# ADC.net
KiCad netlist of a schematic drawn in Altium Designer
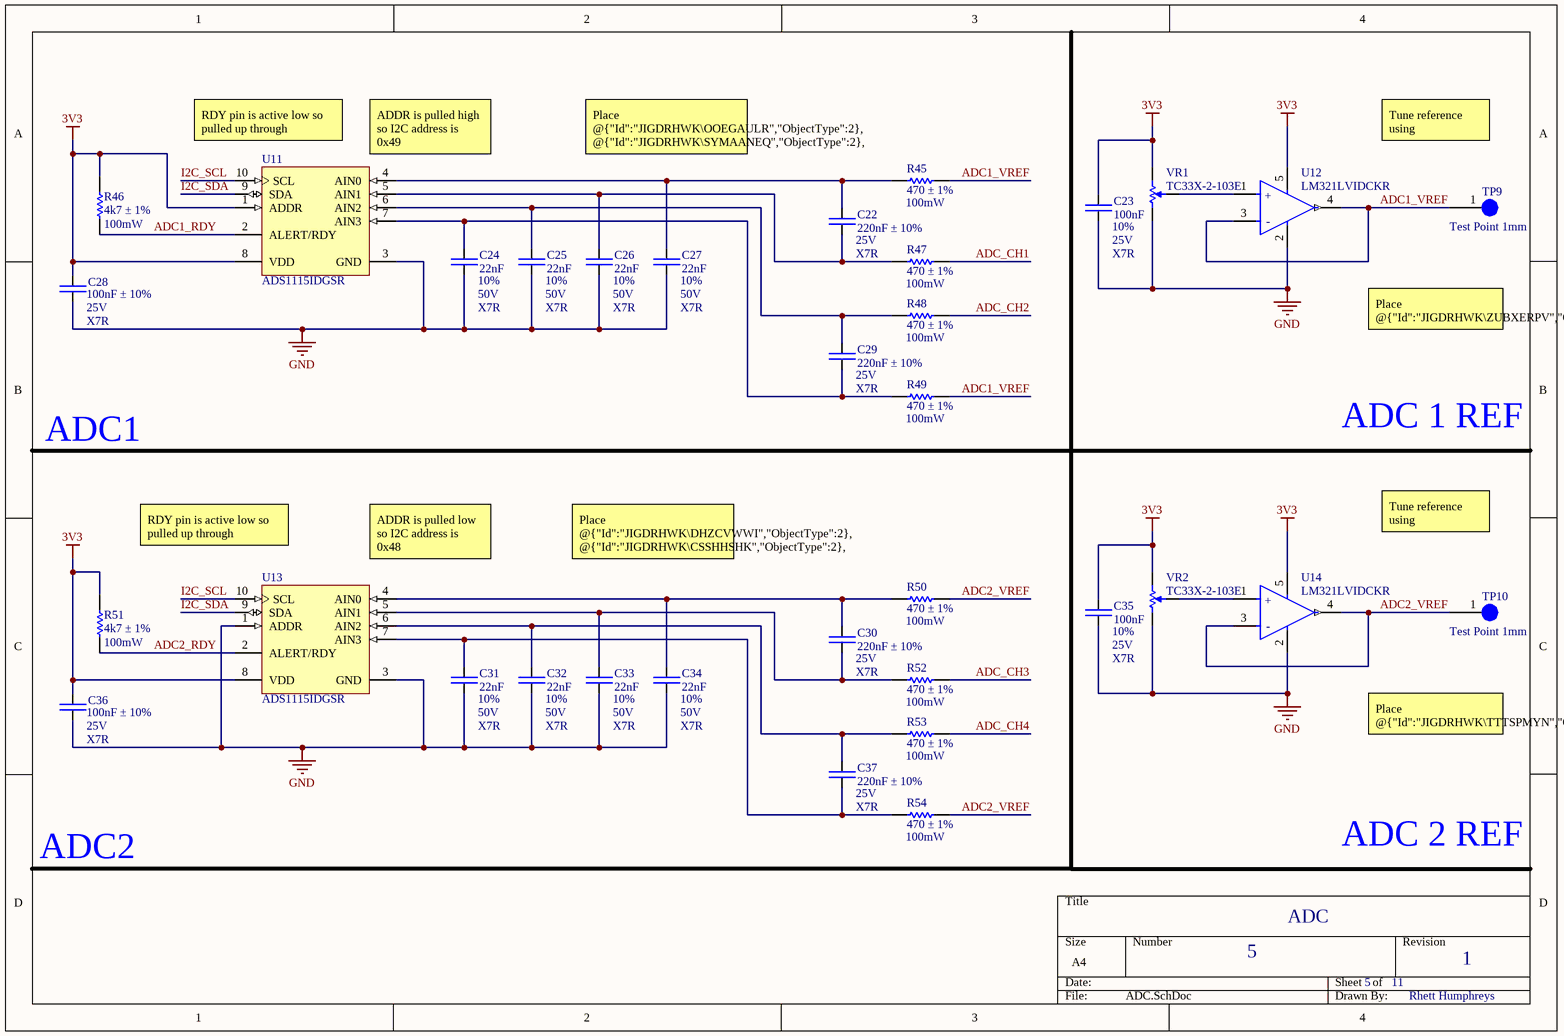
[diagram p0: ADC.SchDoc]

(export (version "E")
  (design (tool "Eeschema 10.0.6"))
  (components
    (comp (ref "C22")
      (value "220nF ± 10%")
      (footprint "CAP-0603")
      (description "Capacitor chip unpolarized. 0603")
      (libsource (lib "Master") (part "CAP-0603"))
    )
    (comp (ref "C23")
      (value "100nF")
      (footprint "CAP-0603")
      (description "Capacitor chip unpolarized. 0603")
      (libsource (lib "Master") (part "CAP-0603"))
    )
    (comp (ref "C24")
      (value "22nF")
      (footprint "CAP-0603")
      (description "Capacitor chip unpolarized. 0603")
      (libsource (lib "Master") (part "CAP-0603"))
    )
    (comp (ref "C25")
      (value "22nF")
      (footprint "CAP-0603")
      (description "Capacitor chip unpolarized. 0603")
      (libsource (lib "Master") (part "CAP-0603"))
    )
    (comp (ref "C26")
      (value "22nF")
      (footprint "CAP-0603")
      (description "Capacitor chip unpolarized. 0603")
      (libsource (lib "Master") (part "CAP-0603"))
    )
    (comp (ref "C27")
      (value "22nF")
      (footprint "CAP-0603")
      (description "Capacitor chip unpolarized. 0603")
      (libsource (lib "Master") (part "CAP-0603"))
    )
    (comp (ref "C28")
      (value "100nF ± 10%")
      (footprint "CAP-0603")
      (description "Capacitor chip unpolarized. 0603")
      (libsource (lib "Master") (part "CAP-0603"))
    )
    (comp (ref "C29")
      (value "220nF ± 10%")
      (footprint "CAP-0603")
      (description "Capacitor chip unpolarized. 0603")
      (libsource (lib "Master") (part "CAP-0603"))
    )
    (comp (ref "C30")
      (value "220nF ± 10%")
      (footprint "CAP-0603")
      (description "Capacitor chip unpolarized. 0603")
      (libsource (lib "Master") (part "CAP-0603"))
    )
    (comp (ref "C31")
      (value "22nF")
      (footprint "CAP-0603")
      (description "Capacitor chip unpolarized. 0603")
      (libsource (lib "Master") (part "CAP-0603"))
    )
    (comp (ref "C32")
      (value "22nF")
      (footprint "CAP-0603")
      (description "Capacitor chip unpolarized. 0603")
      (libsource (lib "Master") (part "CAP-0603"))
    )
    (comp (ref "C33")
      (value "22nF")
      (footprint "CAP-0603")
      (description "Capacitor chip unpolarized. 0603")
      (libsource (lib "Master") (part "CAP-0603"))
    )
    (comp (ref "C34")
      (value "22nF")
      (footprint "CAP-0603")
      (description "Capacitor chip unpolarized. 0603")
      (libsource (lib "Master") (part "CAP-0603"))
    )
    (comp (ref "C35")
      (value "100nF")
      (footprint "CAP-0603")
      (description "Capacitor chip unpolarized. 0603")
      (libsource (lib "Master") (part "CAP-0603"))
    )
    (comp (ref "C36")
      (value "100nF ± 10%")
      (footprint "CAP-0603")
      (description "Capacitor chip unpolarized. 0603")
      (libsource (lib "Master") (part "CAP-0603"))
    )
    (comp (ref "C37")
      (value "220nF ± 10%")
      (footprint "CAP-0603")
      (description "Capacitor chip unpolarized. 0603")
      (libsource (lib "Master") (part "CAP-0603"))
    )
    (comp (ref "R45")
      (value "470 ± 1%")
      (footprint "RES-0603")
      (description "Resistor chip. 0603")
      (libsource (lib "Master") (part "RES-0603"))
    )
    (comp (ref "R46")
      (value "4k7 ± 1%")
      (footprint "RES-0603")
      (description "Resistor chip. 0603")
      (libsource (lib "Master") (part "RES-0603"))
    )
    (comp (ref "R47")
      (value "470 ± 1%")
      (footprint "RES-0603")
      (description "Resistor chip. 0603")
      (libsource (lib "Master") (part "RES-0603"))
    )
    (comp (ref "R48")
      (value "470 ± 1%")
      (footprint "RES-0603")
      (description "Resistor chip. 0603")
      (libsource (lib "Master") (part "RES-0603"))
    )
    (comp (ref "R49")
      (value "470 ± 1%")
      (footprint "RES-0603")
      (description "Resistor chip. 0603")
      (libsource (lib "Master") (part "RES-0603"))
    )
    (comp (ref "R50")
      (value "470 ± 1%")
      (footprint "RES-0603")
      (description "Resistor chip. 0603")
      (libsource (lib "Master") (part "RES-0603"))
    )
    (comp (ref "R51")
      (value "4k7 ± 1%")
      (footprint "RES-0603")
      (description "Resistor chip. 0603")
      (libsource (lib "Master") (part "RES-0603"))
    )
    (comp (ref "R52")
      (value "470 ± 1%")
      (footprint "RES-0603")
      (description "Resistor chip. 0603")
      (libsource (lib "Master") (part "RES-0603"))
    )
    (comp (ref "R53")
      (value "470 ± 1%")
      (footprint "RES-0603")
      (description "Resistor chip. 0603")
      (libsource (lib "Master") (part "RES-0603"))
    )
    (comp (ref "R54")
      (value "470 ± 1%")
      (footprint "RES-0603")
      (description "Resistor chip. 0603")
      (libsource (lib "Master") (part "RES-0603"))
    )
    (comp (ref "TP9")
      (value "Test Point 1mm")
      (footprint "Test Point 1mm")
      (libsource (lib "Master") (part "Test Point 1mm"))
    )
    (comp (ref "TP10")
      (value "Test Point 1mm")
      (footprint "Test Point 1mm")
      (libsource (lib "Master") (part "Test Point 1mm"))
    )
    (comp (ref "U11")
      (value "ADS1115IDGSR")
      (footprint "TI-DGS10_M")
      (fields (field (name "PARTNUMBER") "ADS1115IDGST") (field (name "MANUFACTURER") "Texas Instruments"))
      (libsource (lib "Altium Content Vault") (part "TI-ADS1015_1115-10"))
    )
    (comp (ref "U12")
      (value "LM321LVIDCKR")
      (footprint "FP-DCK0005A-IPC_B")
      (description "IC OPAMP GP 1 CIRCUIT SC70-5")
      (libsource (lib "Altium Content Vault") (part "471d8b929410cd356ad4b122f572ce5"))
    )
    (comp (ref "U13")
      (value "ADS1115IDGSR")
      (footprint "TI-DGS10_M")
      (fields (field (name "PARTNUMBER") "ADS1115IDGST") (field (name "MANUFACTURER") "Texas Instruments"))
      (libsource (lib "Altium Content Vault") (part "TI-ADS1015_1115-10"))
    )
    (comp (ref "U14")
      (value "LM321LVIDCKR")
      (footprint "FP-DCK0005A-IPC_B")
      (description "IC OPAMP GP 1 CIRCUIT SC70-5")
      (libsource (lib "Altium Content Vault") (part "471d8b929410cd356ad4b122f572ce5"))
    )
    (comp (ref "VR1")
      (value "TC33X-2-103E")
      (footprint "BOUR-TC33X-2_V")
      (description "Trimming Potentiometer, 10000 Ohm, -40 to 100 degC, 3-Pin SMD, RoHS, Tape and Reel")
      (fields (field (name "TOLERANCE") "25%") (field (name "MANUFACTURER") "Bourns"))
      (libsource (lib "Altium Content Vault") (part "RES-ADJ-3_A"))
    )
    (comp (ref "VR2")
      (value "TC33X-2-103E")
      (footprint "BOUR-TC33X-2_V")
      (description "Trimming Potentiometer, 10000 Ohm, -40 to 100 degC, 3-Pin SMD, RoHS, Tape and Reel")
      (fields (field (name "TOLERANCE") "25%") (field (name "MANUFACTURER") "Bourns"))
      (libsource (lib "Altium Content Vault") (part "RES-ADJ-3_A"))
    )
  )
  (nets
    (net (code "1") (name "/ADC1_RDY") (class "Default")
      (node (ref "R46") (pin "1") (pintype "passive"))
      (node (ref "U11") (pin "2") (pinfunction "ALERT/RDY_2") (pintype "open_collector"))
    )
    (net (code "2") (name "/ADC1_VREF") (class "Default")
      (node (ref "R45") (pin "1") (pintype "passive"))
      (node (ref "R49") (pin "1") (pintype "passive"))
      (node (ref "TP9") (pin "1") (pintype "passive"))
      (node (ref "U12") (pin "3") (pinfunction "IN-_3") (pintype "tri_state"))
      (node (ref "U12") (pin "4") (pinfunction "OUT_4") (pintype "output"))
    )
    (net (code "3") (name "/ADC2_RDY") (class "Default")
      (node (ref "R51") (pin "1") (pintype "passive"))
      (node (ref "U13") (pin "2") (pinfunction "ALERT/RDY_2") (pintype "open_collector"))
    )
    (net (code "4") (name "/ADC2_VREF") (class "Default")
      (node (ref "R50") (pin "1") (pintype "passive"))
      (node (ref "R54") (pin "1") (pintype "passive"))
      (node (ref "TP10") (pin "1") (pintype "passive"))
      (node (ref "U14") (pin "3") (pinfunction "IN-_3") (pintype "tri_state"))
      (node (ref "U14") (pin "4") (pinfunction "OUT_4") (pintype "output"))
    )
    (net (code "5") (name "/ADC_CH1") (class "Default") (node (ref "R47") (pin "1") (pintype "passive")))
    (net (code "6") (name "/ADC_CH2") (class "Default") (node (ref "R48") (pin "1") (pintype "passive")))
    (net (code "7") (name "/ADC_CH3") (class "Default") (node (ref "R52") (pin "1") (pintype "passive")))
    (net (code "8") (name "/ADC_CH4") (class "Default") (node (ref "R53") (pin "1") (pintype "passive")))
    (net (code "9") (name "/I2C_SCL") (class "Default")
      (node (ref "U11") (pin "10") (pinfunction "SCL_10") (pintype "input"))
      (node (ref "U13") (pin "10") (pinfunction "SCL_10") (pintype "input"))
    )
    (net (code "10") (name "/I2C_SDA") (class "Default")
      (node (ref "U11") (pin "9") (pinfunction "SDA_9") (pintype "bidirectional"))
      (node (ref "U13") (pin "9") (pinfunction "SDA_9") (pintype "bidirectional"))
    )
    (net (code "11") (name "3V3") (class "Default")
      (node (ref "C23") (pin "2") (pintype "passive"))
      (node (ref "C28") (pin "2") (pintype "passive"))
      (node (ref "C35") (pin "2") (pintype "passive"))
      (node (ref "C36") (pin "2") (pintype "passive"))
      (node (ref "R46") (pin "2") (pintype "passive"))
      (node (ref "R51") (pin "2") (pintype "passive"))
      (node (ref "U11") (pin "1") (pinfunction "ADDR_1") (pintype "input"))
      (node (ref "U11") (pin "8") (pinfunction "VDD_8") (pintype "power_in"))
      (node (ref "U12") (pin "5") (pinfunction "V+_5") (pintype "power_in"))
      (node (ref "U13") (pin "8") (pinfunction "VDD_8") (pintype "power_in"))
      (node (ref "U14") (pin "5") (pinfunction "V+_5") (pintype "power_in"))
      (node (ref "VR1") (pin "3") (pinfunction "3_3") (pintype "passive"))
      (node (ref "VR2") (pin "3") (pinfunction "3_3") (pintype "passive"))
    )
    (net (code "12") (name "GND") (class "Default")
      (node (ref "C23") (pin "1") (pintype "passive"))
      (node (ref "C24") (pin "1") (pintype "passive"))
      (node (ref "C25") (pin "1") (pintype "passive"))
      (node (ref "C26") (pin "1") (pintype "passive"))
      (node (ref "C27") (pin "1") (pintype "passive"))
      (node (ref "C28") (pin "1") (pintype "passive"))
      (node (ref "C31") (pin "1") (pintype "passive"))
      (node (ref "C32") (pin "1") (pintype "passive"))
      (node (ref "C33") (pin "1") (pintype "passive"))
      (node (ref "C34") (pin "1") (pintype "passive"))
      (node (ref "C35") (pin "1") (pintype "passive"))
      (node (ref "C36") (pin "1") (pintype "passive"))
      (node (ref "U11") (pin "3") (pinfunction "GND_3") (pintype "power_in"))
      (node (ref "U12") (pin "2") (pinfunction "V-_2") (pintype "power_in"))
      (node (ref "U13") (pin "1") (pinfunction "ADDR_1") (pintype "input"))
      (node (ref "U13") (pin "3") (pinfunction "GND_3") (pintype "power_in"))
      (node (ref "U14") (pin "2") (pinfunction "V-_2") (pintype "power_in"))
      (node (ref "VR1") (pin "1") (pinfunction "1_1") (pintype "passive"))
      (node (ref "VR2") (pin "1") (pinfunction "1_1") (pintype "passive"))
    )
    (net (code "13") (name "Net-(U11-AIN0)") (class "Default")
      (node (ref "C22") (pin "2") (pintype "passive"))
      (node (ref "C27") (pin "2") (pintype "passive"))
      (node (ref "R45") (pin "2") (pintype "passive"))
      (node (ref "U11") (pin "4") (pinfunction "AIN0_4") (pintype "input"))
    )
    (net (code "14") (name "Net-(U11-AIN1)") (class "Default")
      (node (ref "C22") (pin "1") (pintype "passive"))
      (node (ref "C26") (pin "2") (pintype "passive"))
      (node (ref "R47") (pin "2") (pintype "passive"))
      (node (ref "U11") (pin "5") (pinfunction "AIN1_5") (pintype "input"))
    )
    (net (code "15") (name "Net-(U11-AIN2)") (class "Default")
      (node (ref "C25") (pin "2") (pintype "passive"))
      (node (ref "C29") (pin "2") (pintype "passive"))
      (node (ref "R48") (pin "2") (pintype "passive"))
      (node (ref "U11") (pin "6") (pinfunction "AIN2_6") (pintype "input"))
    )
    (net (code "16") (name "Net-(U11-AIN3)") (class "Default")
      (node (ref "C24") (pin "2") (pintype "passive"))
      (node (ref "C29") (pin "1") (pintype "passive"))
      (node (ref "R49") (pin "2") (pintype "passive"))
      (node (ref "U11") (pin "7") (pinfunction "AIN3_7") (pintype "input"))
    )
    (net (code "17") (name "Net-(U12-IN+)") (class "Default")
      (node (ref "U12") (pin "1") (pinfunction "IN+_1") (pintype "tri_state"))
      (node (ref "VR1") (pin "2") (pinfunction "2_2") (pintype "passive"))
    )
    (net (code "18") (name "Net-(U13-AIN0)") (class "Default")
      (node (ref "C30") (pin "2") (pintype "passive"))
      (node (ref "C34") (pin "2") (pintype "passive"))
      (node (ref "R50") (pin "2") (pintype "passive"))
      (node (ref "U13") (pin "4") (pinfunction "AIN0_4") (pintype "input"))
    )
    (net (code "19") (name "Net-(U13-AIN1)") (class "Default")
      (node (ref "C30") (pin "1") (pintype "passive"))
      (node (ref "C33") (pin "2") (pintype "passive"))
      (node (ref "R52") (pin "2") (pintype "passive"))
      (node (ref "U13") (pin "5") (pinfunction "AIN1_5") (pintype "input"))
    )
    (net (code "20") (name "Net-(U13-AIN2)") (class "Default")
      (node (ref "C32") (pin "2") (pintype "passive"))
      (node (ref "C37") (pin "2") (pintype "passive"))
      (node (ref "R53") (pin "2") (pintype "passive"))
      (node (ref "U13") (pin "6") (pinfunction "AIN2_6") (pintype "input"))
    )
    (net (code "21") (name "Net-(U13-AIN3)") (class "Default")
      (node (ref "C31") (pin "2") (pintype "passive"))
      (node (ref "C37") (pin "1") (pintype "passive"))
      (node (ref "R54") (pin "2") (pintype "passive"))
      (node (ref "U13") (pin "7") (pinfunction "AIN3_7") (pintype "input"))
    )
    (net (code "22") (name "Net-(U14-IN+)") (class "Default")
      (node (ref "U14") (pin "1") (pinfunction "IN+_1") (pintype "tri_state"))
      (node (ref "VR2") (pin "2") (pinfunction "2_2") (pintype "passive"))
    )
  )
)
